# LM1875_AmpCircuit.net
KiCad netlist of a schematic drawn in EAGLE
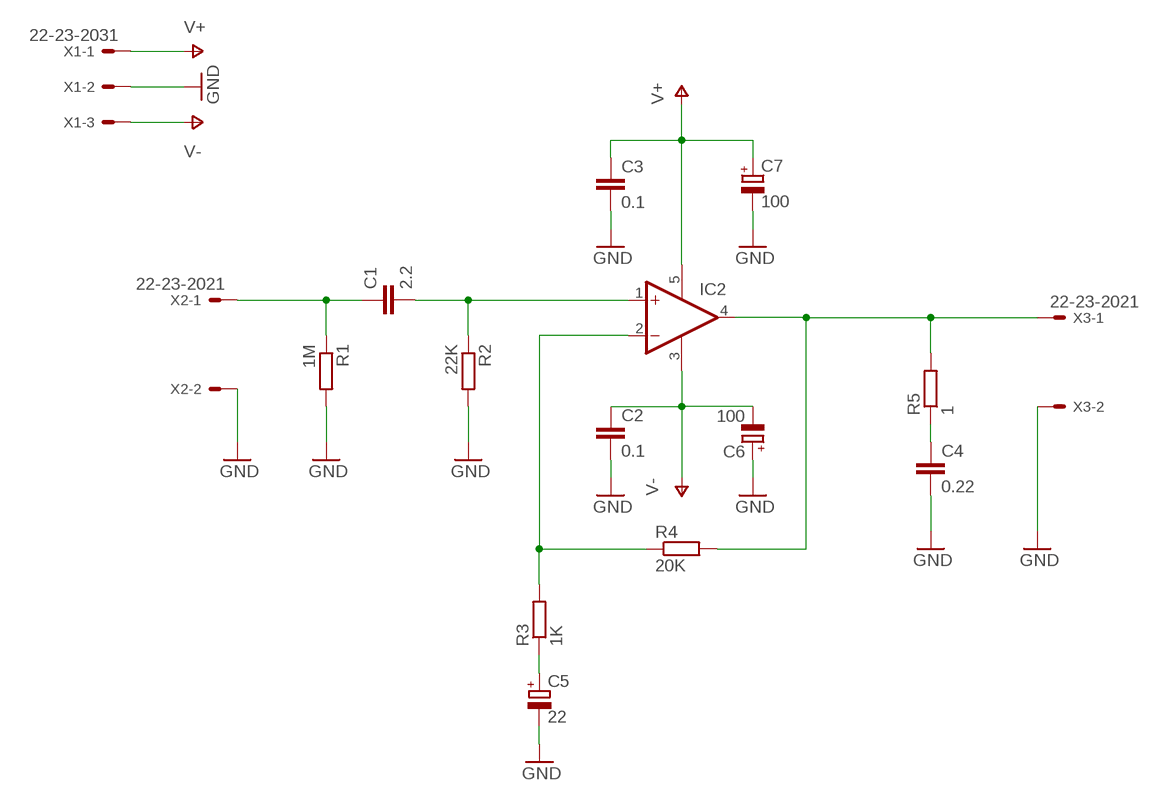
[diagram p0: schematic, sheet 1]

(export (version "E")
  (design (tool "Eeschema 10.0.6"))
  (components
    (comp (ref "C1")
      (value "2.2")
      (footprint "eagle-import:C050-024X044")
      (libsource (lib "eagle-import") (part "C-EU050-024X044"))
    )
    (comp (ref "C2")
      (value "0.1")
      (footprint "eagle-import:C050-024X044")
      (libsource (lib "eagle-import") (part "C-EU050-024X044"))
    )
    (comp (ref "C3")
      (value "0.1")
      (footprint "eagle-import:C050-024X044")
      (libsource (lib "eagle-import") (part "C-EU050-024X044"))
    )
    (comp (ref "C4")
      (value "0.22")
      (footprint "eagle-import:C050-024X044")
      (libsource (lib "eagle-import") (part "C-EU050-024X044"))
    )
    (comp (ref "C5")
      (value "22")
      (footprint "eagle-import:E3,5-10")
      (libsource (lib "eagle-import") (part "CPOL-EUE3.5-10"))
    )
    (comp (ref "C6")
      (value "100")
      (footprint "eagle-import:E3,5-10")
      (libsource (lib "eagle-import") (part "CPOL-EUE3.5-10"))
    )
    (comp (ref "C7")
      (value "100")
      (footprint "eagle-import:E3,5-10")
      (libsource (lib "eagle-import") (part "CPOL-EUE3.5-10"))
    )
    (comp (ref "IC2")
      (value "LM1875TO220-5")
      (footprint "eagle-import:CB360")
      (libsource (lib "eagle-import") (part "LM1875TO220-5"))
    )
    (comp (ref "R1")
      (value "1M")
      (footprint "eagle-import:0204_7")
      (libsource (lib "eagle-import") (part "R-EU_0204/7"))
    )
    (comp (ref "R2")
      (value "22K")
      (footprint "eagle-import:0204_7")
      (libsource (lib "eagle-import") (part "R-EU_0204/7"))
    )
    (comp (ref "R3")
      (value "1K")
      (footprint "eagle-import:0204_7")
      (libsource (lib "eagle-import") (part "R-EU_0204/7"))
    )
    (comp (ref "R4")
      (value "20K")
      (footprint "eagle-import:0204_7")
      (libsource (lib "eagle-import") (part "R-EU_0204/7"))
    )
    (comp (ref "R5")
      (value "1")
      (footprint "eagle-import:0204_7")
      (libsource (lib "eagle-import") (part "R-EU_0204/7"))
    )
    (comp (ref "X1")
      (value "22-23-2031")
      (footprint "eagle-import:22-23-2031")
      (fields (field (name "MF") "MOLEX"))
      (libsource (lib "eagle-import") (part "22-23-2031"))
    )
    (comp (ref "X2")
      (value "22-23-2021")
      (footprint "eagle-import:22-23-2021")
      (fields (field (name "MF") "MOLEX"))
      (libsource (lib "eagle-import") (part "22-23-2021"))
    )
    (comp (ref "X3")
      (value "22-23-2021")
      (footprint "eagle-import:22-23-2021")
      (fields (field (name "MF") "MOLEX"))
      (libsource (lib "eagle-import") (part "22-23-2021"))
    )
  )
  (nets
    (net (code "1") (name "GND") (class "Default")
      (node (ref "C2") (pin "2") (pinfunction "2_2") (pintype "passive"))
      (node (ref "C3") (pin "2") (pinfunction "2_2") (pintype "passive"))
      (node (ref "C4") (pin "2") (pinfunction "2_2") (pintype "passive"))
      (node (ref "C5") (pin "-") (pinfunction "-_-") (pintype "passive"))
      (node (ref "C6") (pin "+") (pinfunction "+_+") (pintype "passive"))
      (node (ref "C7") (pin "-") (pinfunction "-_-") (pintype "passive"))
      (node (ref "R1") (pin "2") (pinfunction "2_2") (pintype "passive"))
      (node (ref "R2") (pin "2") (pinfunction "2_2") (pintype "passive"))
      (node (ref "X1") (pin "2") (pinfunction "S_2") (pintype "passive"))
      (node (ref "X2") (pin "2") (pinfunction "S_2") (pintype "passive"))
      (node (ref "X3") (pin "2") (pinfunction "S_2") (pintype "passive"))
    )
    (net (code "2") (name "Net-(C4-Pad1)") (class "Default")
      (node (ref "C4") (pin "1") (pinfunction "1_1") (pintype "passive"))
      (node (ref "R5") (pin "1") (pinfunction "1_1") (pintype "passive"))
    )
    (net (code "3") (name "Net-(C5-Pad+)") (class "Default")
      (node (ref "C5") (pin "+") (pinfunction "+_+") (pintype "passive"))
      (node (ref "R3") (pin "1") (pinfunction "1_1") (pintype "passive"))
    )
    (net (code "4") (name "Net-(IC2-+IN)") (class "Default")
      (node (ref "C1") (pin "2") (pinfunction "2_2") (pintype "passive"))
      (node (ref "IC2") (pin "1") (pinfunction "+IN_1") (pintype "input"))
      (node (ref "R2") (pin "1") (pinfunction "1_1") (pintype "passive"))
    )
    (net (code "5") (name "Net-(IC2--IN)") (class "Default")
      (node (ref "IC2") (pin "2") (pinfunction "-IN_2") (pintype "input"))
      (node (ref "R3") (pin "2") (pinfunction "2_2") (pintype "passive"))
      (node (ref "R4") (pin "1") (pinfunction "1_1") (pintype "passive"))
    )
    (net (code "6") (name "Net-(IC2-OUT)") (class "Default")
      (node (ref "IC2") (pin "4") (pinfunction "OUT_4") (pintype "output"))
      (node (ref "R4") (pin "2") (pinfunction "2_2") (pintype "passive"))
      (node (ref "R5") (pin "2") (pinfunction "2_2") (pintype "passive"))
      (node (ref "X3") (pin "1") (pinfunction "S_1") (pintype "passive"))
    )
    (net (code "7") (name "Net-(X2A-S)") (class "Default")
      (node (ref "C1") (pin "1") (pinfunction "1_1") (pintype "passive"))
      (node (ref "R1") (pin "1") (pinfunction "1_1") (pintype "passive"))
      (node (ref "X2") (pin "1") (pinfunction "S_1") (pintype "passive"))
    )
    (net (code "8") (name "V+") (class "Default")
      (node (ref "C3") (pin "1") (pinfunction "1_1") (pintype "passive"))
      (node (ref "C7") (pin "+") (pinfunction "+_+") (pintype "passive"))
      (node (ref "IC2") (pin "5") (pinfunction "V+_5") (pintype "power_in"))
      (node (ref "X1") (pin "1") (pinfunction "S_1") (pintype "passive"))
    )
    (net (code "9") (name "V-") (class "Default")
      (node (ref "C2") (pin "1") (pinfunction "1_1") (pintype "passive"))
      (node (ref "C6") (pin "-") (pinfunction "-_-") (pintype "passive"))
      (node (ref "IC2") (pin "3") (pinfunction "V-_3") (pintype "power_in"))
      (node (ref "X1") (pin "3") (pinfunction "S_3") (pintype "passive"))
    )
  )
)
